# untitled_4.net
KiCad netlist of a schematic drawn in EAGLE
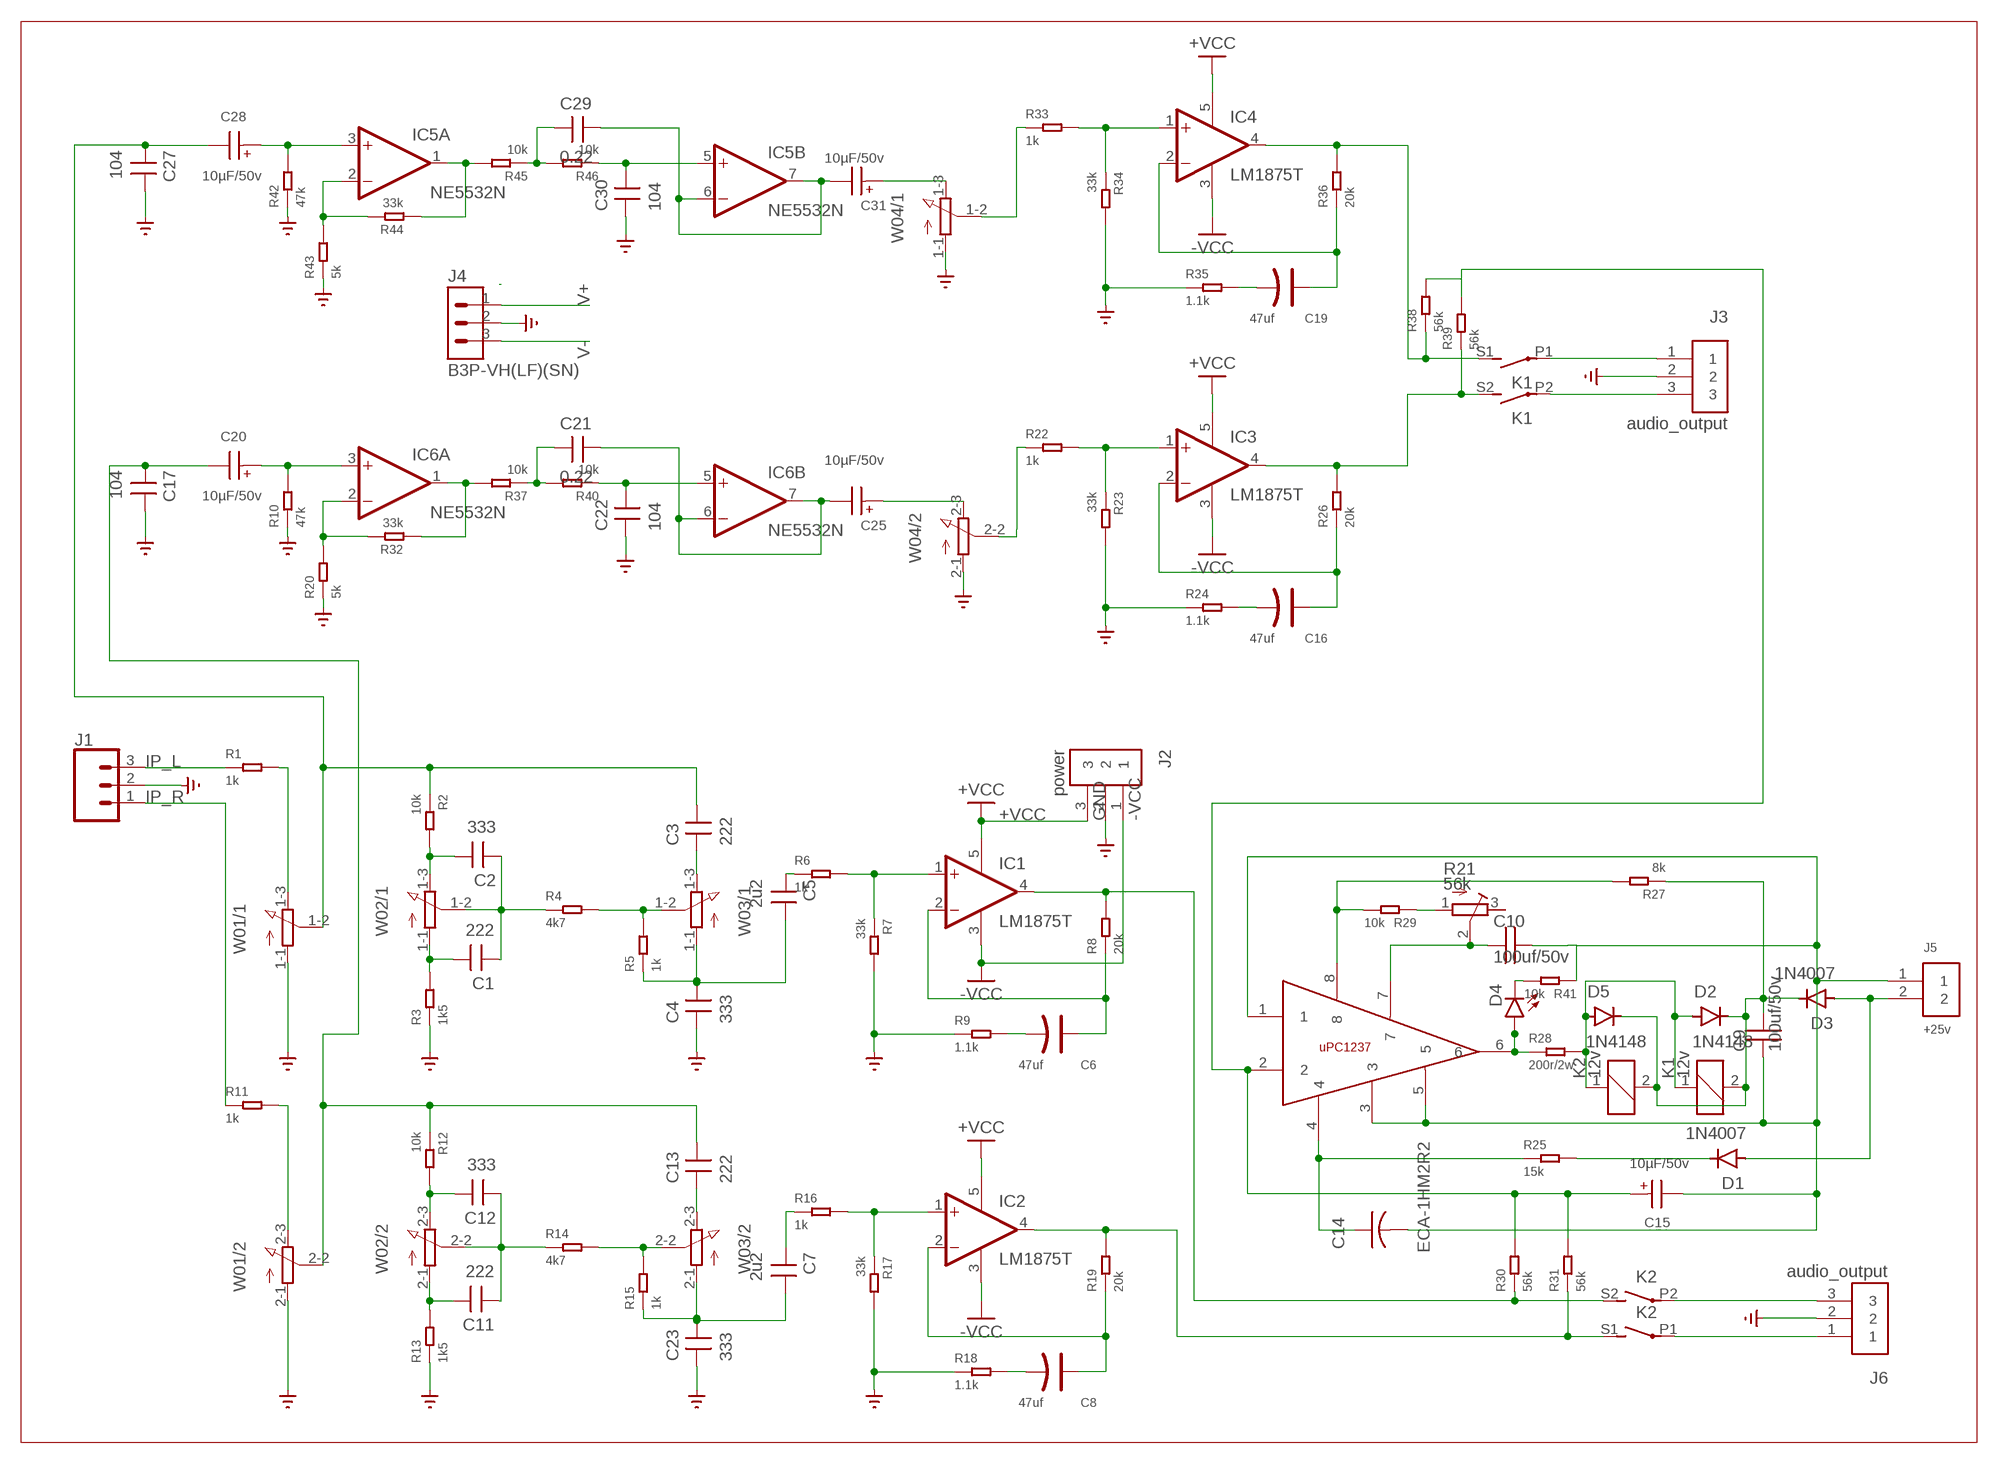
[diagram p0: schematic, sheet 1]

(export (version "E")
  (design (tool "Eeschema 10.0.6"))
  (components
    (comp (ref "C1")
      (value "222")
      (footprint "eagle-import:5.08MM-独石电容")
      (libsource (lib "eagle-import") (part "5.08MM-"))
    )
    (comp (ref "C2")
      (value "333")
      (footprint "eagle-import:5.08MM-独石电容")
      (libsource (lib "eagle-import") (part "5.08MM-"))
    )
    (comp (ref "C3")
      (value "222")
      (footprint "eagle-import:5.08MM-独石电容")
      (libsource (lib "eagle-import") (part "5.08MM-"))
    )
    (comp (ref "C4")
      (value "333")
      (footprint "eagle-import:5.08MM-独石电容")
      (libsource (lib "eagle-import") (part "5.08MM-"))
    )
    (comp (ref "C5")
      (value "2u2")
      (footprint "eagle-import:5.08MM-独石电容")
      (libsource (lib "eagle-import") (part "5.08MM-"))
    )
    (comp (ref "C6")
      (value "47uf")
      (footprint "eagle-import:PC-D5.3MM")
      (fields (field (name "MPN") "KS 100uF/16V"))
      (libsource (lib "eagle-import") (part "DIP-ALUMINUM-47UF-16V(D5-H7MM)"))
    )
    (comp (ref "C7")
      (value "2u2")
      (footprint "eagle-import:5.08MM-独石电容")
      (libsource (lib "eagle-import") (part "5.08MM-"))
    )
    (comp (ref "C8")
      (value "47uf")
      (footprint "eagle-import:PC-D5.3MM")
      (fields (field (name "MPN") "KS 100uF/16V"))
      (libsource (lib "eagle-import") (part "DIP-ALUMINUM-47UF-16V(D5-H7MM)"))
    )
    (comp (ref "C9")
      (value "100uf/50v")
      (footprint "eagle-import:8X12")
      (libsource (lib "eagle-import") (part "50V100UF8X12"))
    )
    (comp (ref "C10")
      (value "100uf/50v")
      (footprint "eagle-import:8X12")
      (libsource (lib "eagle-import") (part "50V100UF8X12"))
    )
    (comp (ref "C11")
      (value "222")
      (footprint "eagle-import:5.08MM-独石电容")
      (libsource (lib "eagle-import") (part "5.08MM-"))
    )
    (comp (ref "C12")
      (value "333")
      (footprint "eagle-import:5.08MM-独石电容")
      (libsource (lib "eagle-import") (part "5.08MM-"))
    )
    (comp (ref "C13")
      (value "222")
      (footprint "eagle-import:5.08MM-独石电容")
      (libsource (lib "eagle-import") (part "5.08MM-"))
    )
    (comp (ref "C14")
      (value "ECA-1HM2R2")
      (footprint "eagle-import:CAP_RADIAL_2MM")
      (fields
        (field (name "DIGIKEY_PART_NUMBER") "P5175-ND")
        (field (name "MANUFACTURER") "Panasonic Electronic Components")
        (field (name "CREATED_BY") "PCBLayout.com")
      )
      (libsource (lib "eagle-import") (part "ECA-1HM2R2"))
    )
    (comp (ref "C15")
      (value "10µF/50v")
      (footprint "eagle-import:WCAP-AT1H_5X11(DXL)")
      (libsource (lib "eagle-import") (part "WCAP-AT1H_5X11_860240272001"))
    )
    (comp (ref "C16")
      (value "47uf")
      (footprint "eagle-import:PC-D5.3MM")
      (fields (field (name "MPN") "KS 100uF/16V"))
      (libsource (lib "eagle-import") (part "DIP-ALUMINUM-47UF-16V(D5-H7MM)"))
    )
    (comp (ref "C17")
      (value "104")
      (footprint "eagle-import:5.08MM-独石电容")
      (libsource (lib "eagle-import") (part "5.08MM-"))
    )
    (comp (ref "C19")
      (value "47uf")
      (footprint "eagle-import:PC-D5.3MM")
      (fields (field (name "MPN") "KS 100uF/16V"))
      (libsource (lib "eagle-import") (part "DIP-ALUMINUM-47UF-16V(D5-H7MM)"))
    )
    (comp (ref "C20")
      (value "10µF/50v")
      (footprint "eagle-import:WCAP-AT1H_5X11(DXL)")
      (libsource (lib "eagle-import") (part "WCAP-AT1H_5X11_860240272001"))
    )
    (comp (ref "C21")
      (value "0.22")
      (footprint "eagle-import:5.08MM-独石电容")
      (libsource (lib "eagle-import") (part "5.08MM-"))
    )
    (comp (ref "C22")
      (value "104")
      (footprint "eagle-import:5.08MM-独石电容")
      (libsource (lib "eagle-import") (part "5.08MM-"))
    )
    (comp (ref "C23")
      (value "333")
      (footprint "eagle-import:5.08MM-独石电容")
      (libsource (lib "eagle-import") (part "5.08MM-"))
    )
    (comp (ref "C25")
      (value "10µF/50v")
      (footprint "eagle-import:WCAP-AT1H_5X11(DXL)")
      (libsource (lib "eagle-import") (part "WCAP-AT1H_5X11_860240272001"))
    )
    (comp (ref "C27")
      (value "104")
      (footprint "eagle-import:5.08MM-独石电容")
      (libsource (lib "eagle-import") (part "5.08MM-"))
    )
    (comp (ref "C28")
      (value "10µF/50v")
      (footprint "eagle-import:WCAP-AT1H_5X11(DXL)")
      (libsource (lib "eagle-import") (part "WCAP-AT1H_5X11_860240272001"))
    )
    (comp (ref "C29")
      (value "0.22")
      (footprint "eagle-import:5.08MM-独石电容")
      (libsource (lib "eagle-import") (part "5.08MM-"))
    )
    (comp (ref "C30")
      (value "104")
      (footprint "eagle-import:5.08MM-独石电容")
      (libsource (lib "eagle-import") (part "5.08MM-"))
    )
    (comp (ref "C31")
      (value "10µF/50v")
      (footprint "eagle-import:WCAP-AT1H_5X11(DXL)")
      (libsource (lib "eagle-import") (part "WCAP-AT1H_5X11_860240272001"))
    )
    (comp (ref "D1")
      (value "1N4007")
      (footprint "eagle-import:DO-41")
      (fields
        (field (name "DIGIKEY_PART_NUMBER") "1N4007MSCT-ND")
        (field (name "MANUFACTURER") "Micro Commercial Co")
        (field (name "CREATED_BY") "PCBLayout.com")
      )
      (libsource (lib "eagle-import") (part "1N4007"))
    )
    (comp (ref "D2")
      (value "1N4148")
      (footprint "eagle-import:DO-41")
      (fields
        (field (name "DIGIKEY_PART_NUMBER") "1N4007MSCT-ND")
        (field (name "MANUFACTURER") "Micro Commercial Co")
        (field (name "MPN") "1N4007")
        (field (name "CREATED_BY") "PCBLayout.com")
      )
      (libsource (lib "eagle-import") (part "1N4007"))
    )
    (comp (ref "D3")
      (value "1N4007")
      (footprint "eagle-import:DO-41")
      (fields
        (field (name "DIGIKEY_PART_NUMBER") "1N4007MSCT-ND")
        (field (name "MANUFACTURER") "Micro Commercial Co")
        (field (name "CREATED_BY") "PCBLayout.com")
      )
      (libsource (lib "eagle-import") (part "1N4007"))
    )
    (comp (ref "D4")
      (value "BEAGLEBONE_BLUE_LED-3MM-NO_SILK")
      (footprint "eagle-import:BEAGLEBONE_BLUE_BEAGLEBONE_BLUE_LED3MM-NS")
      (libsource (lib "eagle-import") (part "BEAGLEBONE_BLUE_LED-3MM-NO_SILK"))
    )
    (comp (ref "D5")
      (value "1N4148")
      (footprint "eagle-import:DO-41")
      (fields
        (field (name "DIGIKEY_PART_NUMBER") "1N4007MSCT-ND")
        (field (name "MANUFACTURER") "Micro Commercial Co")
        (field (name "MPN") "1N4007")
        (field (name "CREATED_BY") "PCBLayout.com")
      )
      (libsource (lib "eagle-import") (part "1N4007"))
    )
    (comp (ref "IC1")
      (value "LM1875T")
      (footprint "eagle-import:CB367")
      (libsource (lib "eagle-import") (part "LM1875T"))
    )
    (comp (ref "IC2")
      (value "LM1875T")
      (footprint "eagle-import:CB367")
      (libsource (lib "eagle-import") (part "LM1875T"))
    )
    (comp (ref "IC3")
      (value "LM1875T")
      (footprint "eagle-import:CB367")
      (libsource (lib "eagle-import") (part "LM1875T"))
    )
    (comp (ref "IC4")
      (value "LM1875T")
      (footprint "eagle-import:CB367")
      (libsource (lib "eagle-import") (part "LM1875T"))
    )
    (comp (ref "IC5")
      (value "NE5532N")
      (footprint "eagle-import:DIL08")
      (libsource (lib "eagle-import") (part "NE5532N"))
    )
    (comp (ref "IC6")
      (value "NE5532N")
      (footprint "eagle-import:DIL08")
      (libsource (lib "eagle-import") (part "NE5532N"))
    )
    (comp (ref "J1")
      (value "CONN_03POLAR")
      (footprint "eagle-import:MOLEX-1X3")
      (libsource (lib "eagle-import") (part "CONN_03POLAR"))
    )
    (comp (ref "J2")
      (value "power")
      (footprint "eagle-import:TERMINALBLOCK_PLUGGABLE-3-7.62MM")
      (fields
        (field (name "DIGIKEY_PART_NO") "732-2824-ND")
        (field (name "MANUFACTURER") "WURTH ELEKTRONIK")
        (field (name "MPN") "691311400103")
        (field (name "CREATED_BY") "PCBLayout.com")
      )
      (libsource (lib "eagle-import") (part "691311400103"))
    )
    (comp (ref "J3")
      (value "audio_output")
      (footprint "eagle-import:TERMINALBLOCK_PLUGGABLE-3-7.62MM")
      (fields
        (field (name "DIGIKEY_PART_NO") "732-2824-ND")
        (field (name "MANUFACTURER") "WURTH ELEKTRONIK")
        (field (name "MPN") "691311400103")
        (field (name "CREATED_BY") "PCBLayout.com")
      )
      (libsource (lib "eagle-import") (part "691311400103"))
    )
    (comp (ref "J4")
      (value "B3P-VH(LF)(SN)")
      (footprint "eagle-import:HDR-03")
      (fields
        (field (name "DIGIKEY_PART_NUMBER") "455-1640-ND")
        (field (name "MANUFACTURER") "JST Sales America Inc.")
        (field (name "CREATED_BY") "PCBLayout.com")
      )
      (libsource (lib "eagle-import") (part "B3P-VH(LF)(SN)"))
    )
    (comp (ref "J5")
      (value "+25v")
      (footprint "eagle-import:S2B-PH-K-S(LF)(SN)")
      (fields
        (field (name "DIGI_KEY_PART_NUMBER") "455-1719-ND")
        (field (name "MANUFACTURER") "JST Sales America Inc.")
        (field (name "MPN") "S2B-PH-K-S(LF)(SN)")
        (field (name "CREATED_BY") "PCBLayout.com")
      )
      (libsource (lib "eagle-import") (part "S2B-PH-K-S(LF)(SN)"))
    )
    (comp (ref "J6")
      (value "audio_output")
      (footprint "eagle-import:TERMINALBLOCK_PLUGGABLE-3-7.62MM")
      (fields
        (field (name "DIGIKEY_PART_NO") "732-2824-ND")
        (field (name "MANUFACTURER") "WURTH ELEKTRONIK")
        (field (name "MPN") "691311400103")
        (field (name "CREATED_BY") "PCBLayout.com")
      )
      (libsource (lib "eagle-import") (part "691311400103"))
    )
    (comp (ref "K1")
      (value "12v")
      (footprint "eagle-import:G2R2A")
      (fields (field (name "MPN") "G2R-2A-DC24"))
      (libsource (lib "eagle-import") (part "G2R2A"))
    )
    (comp (ref "K2")
      (value "12v")
      (footprint "eagle-import:G2R2A")
      (fields (field (name "MPN") "G2R-2A-DC24"))
      (libsource (lib "eagle-import") (part "G2R2A"))
    )
    (comp (ref "R1")
      (value "1k")
      (footprint "eagle-import:PR-D2.3XL6.5MM")
      (fields (field (name "MPN") "FHCFR-1/4W-105J"))
      (libsource (lib "eagle-import") (part "DIP-RES-1M-5%-1/4W(PR-D2.3XL6.5MM)"))
    )
    (comp (ref "R2")
      (value "10k")
      (footprint "eagle-import:PR-D2.3XL6.5MM")
      (fields (field (name "MPN") "FHCFR-1/4W-105J"))
      (libsource (lib "eagle-import") (part "DIP-RES-1M-5%-1/4W(PR-D2.3XL6.5MM)"))
    )
    (comp (ref "R3")
      (value "1k5")
      (footprint "eagle-import:PR-D2.3XL6.5MM")
      (fields (field (name "MPN") "FHCFR-1/4W-105J"))
      (libsource (lib "eagle-import") (part "DIP-RES-1M-5%-1/4W(PR-D2.3XL6.5MM)"))
    )
    (comp (ref "R4")
      (value "4k7")
      (footprint "eagle-import:PR-D2.3XL6.5MM")
      (fields (field (name "MPN") "FHCFR-1/4W-105J"))
      (libsource (lib "eagle-import") (part "DIP-RES-1M-5%-1/4W(PR-D2.3XL6.5MM)"))
    )
    (comp (ref "R5")
      (value "1k")
      (footprint "eagle-import:PR-D2.3XL6.5MM")
      (fields (field (name "MPN") "FHCFR-1/4W-105J"))
      (libsource (lib "eagle-import") (part "DIP-RES-1M-5%-1/4W(PR-D2.3XL6.5MM)"))
    )
    (comp (ref "R6")
      (value "1k")
      (footprint "eagle-import:PR-D2.3XL6.5MM")
      (fields (field (name "MPN") "FHCFR-1/4W-105J"))
      (libsource (lib "eagle-import") (part "DIP-RES-1M-5%-1/4W(PR-D2.3XL6.5MM)"))
    )
    (comp (ref "R7")
      (value "33k")
      (footprint "eagle-import:PR-D2.3XL6.5MM")
      (fields (field (name "MPN") "FHCFR-1/4W-105J"))
      (libsource (lib "eagle-import") (part "DIP-RES-1M-5%-1/4W(PR-D2.3XL6.5MM)"))
    )
    (comp (ref "R8")
      (value "20k")
      (footprint "eagle-import:PR-D2.3XL6.5MM")
      (fields (field (name "MPN") "FHCFR-1/4W-105J"))
      (libsource (lib "eagle-import") (part "DIP-RES-1M-5%-1/4W(PR-D2.3XL6.5MM)"))
    )
    (comp (ref "R9")
      (value "1.1k")
      (footprint "eagle-import:PR-D2.3XL6.5MM")
      (fields (field (name "MPN") "FHCFR-1/4W-105J"))
      (libsource (lib "eagle-import") (part "DIP-RES-1M-5%-1/4W(PR-D2.3XL6.5MM)"))
    )
    (comp (ref "R10")
      (value "47k")
      (footprint "eagle-import:PR-D2.3XL6.5MM")
      (fields (field (name "MPN") "FHCFR-1/4W-105J"))
      (libsource (lib "eagle-import") (part "DIP-RES-1M-5%-1/4W(PR-D2.3XL6.5MM)"))
    )
    (comp (ref "R11")
      (value "1k")
      (footprint "eagle-import:PR-D2.3XL6.5MM")
      (fields (field (name "MPN") "FHCFR-1/4W-105J"))
      (libsource (lib "eagle-import") (part "DIP-RES-1M-5%-1/4W(PR-D2.3XL6.5MM)"))
    )
    (comp (ref "R12")
      (value "10k")
      (footprint "eagle-import:PR-D2.3XL6.5MM")
      (fields (field (name "MPN") "FHCFR-1/4W-105J"))
      (libsource (lib "eagle-import") (part "DIP-RES-1M-5%-1/4W(PR-D2.3XL6.5MM)"))
    )
    (comp (ref "R13")
      (value "1k5")
      (footprint "eagle-import:PR-D2.3XL6.5MM")
      (fields (field (name "MPN") "FHCFR-1/4W-105J"))
      (libsource (lib "eagle-import") (part "DIP-RES-1M-5%-1/4W(PR-D2.3XL6.5MM)"))
    )
    (comp (ref "R14")
      (value "4k7")
      (footprint "eagle-import:PR-D2.3XL6.5MM")
      (fields (field (name "MPN") "FHCFR-1/4W-105J"))
      (libsource (lib "eagle-import") (part "DIP-RES-1M-5%-1/4W(PR-D2.3XL6.5MM)"))
    )
    (comp (ref "R15")
      (value "1k")
      (footprint "eagle-import:PR-D2.3XL6.5MM")
      (fields (field (name "MPN") "FHCFR-1/4W-105J"))
      (libsource (lib "eagle-import") (part "DIP-RES-1M-5%-1/4W(PR-D2.3XL6.5MM)"))
    )
    (comp (ref "R16")
      (value "1k")
      (footprint "eagle-import:PR-D2.3XL6.5MM")
      (fields (field (name "MPN") "FHCFR-1/4W-105J"))
      (libsource (lib "eagle-import") (part "DIP-RES-1M-5%-1/4W(PR-D2.3XL6.5MM)"))
    )
    (comp (ref "R17")
      (value "33k")
      (footprint "eagle-import:PR-D2.3XL6.5MM")
      (fields (field (name "MPN") "FHCFR-1/4W-105J"))
      (libsource (lib "eagle-import") (part "DIP-RES-1M-5%-1/4W(PR-D2.3XL6.5MM)"))
    )
    (comp (ref "R18")
      (value "1.1k")
      (footprint "eagle-import:PR-D2.3XL6.5MM")
      (fields (field (name "MPN") "FHCFR-1/4W-105J"))
      (libsource (lib "eagle-import") (part "DIP-RES-1M-5%-1/4W(PR-D2.3XL6.5MM)"))
    )
    (comp (ref "R19")
      (value "20k")
      (footprint "eagle-import:PR-D2.3XL6.5MM")
      (fields (field (name "MPN") "FHCFR-1/4W-105J"))
      (libsource (lib "eagle-import") (part "DIP-RES-1M-5%-1/4W(PR-D2.3XL6.5MM)"))
    )
    (comp (ref "R20")
      (value "5k")
      (footprint "eagle-import:PR-D2.3XL6.5MM")
      (fields (field (name "MPN") "FHCFR-1/4W-105J"))
      (libsource (lib "eagle-import") (part "DIP-RES-1M-5%-1/4W(PR-D2.3XL6.5MM)"))
    )
    (comp (ref "R21")
      (value "56k")
      (footprint "eagle-import:RTRIM3296W")
      (libsource (lib "eagle-import") (part "R-TRIMM3296W"))
    )
    (comp (ref "R22")
      (value "1k")
      (footprint "eagle-import:PR-D2.3XL6.5MM")
      (fields (field (name "MPN") "FHCFR-1/4W-105J"))
      (libsource (lib "eagle-import") (part "DIP-RES-1M-5%-1/4W(PR-D2.3XL6.5MM)"))
    )
    (comp (ref "R23")
      (value "33k")
      (footprint "eagle-import:PR-D2.3XL6.5MM")
      (fields (field (name "MPN") "FHCFR-1/4W-105J"))
      (libsource (lib "eagle-import") (part "DIP-RES-1M-5%-1/4W(PR-D2.3XL6.5MM)"))
    )
    (comp (ref "R24")
      (value "1.1k")
      (footprint "eagle-import:PR-D2.3XL6.5MM")
      (fields (field (name "MPN") "FHCFR-1/4W-105J"))
      (libsource (lib "eagle-import") (part "DIP-RES-1M-5%-1/4W(PR-D2.3XL6.5MM)"))
    )
    (comp (ref "R25")
      (value "15k")
      (footprint "eagle-import:PR-D2.3XL6.5MM")
      (fields (field (name "MPN") "FHCFR-1/4W-105J"))
      (libsource (lib "eagle-import") (part "DIP-RES-1M-5%-1/4W(PR-D2.3XL6.5MM)"))
    )
    (comp (ref "R26")
      (value "20k")
      (footprint "eagle-import:PR-D2.3XL6.5MM")
      (fields (field (name "MPN") "FHCFR-1/4W-105J"))
      (libsource (lib "eagle-import") (part "DIP-RES-1M-5%-1/4W(PR-D2.3XL6.5MM)"))
    )
    (comp (ref "R27")
      (value "8k")
      (footprint "eagle-import:PR-D2.3XL6.5MM")
      (fields (field (name "MPN") "FHCFR-1/4W-105J"))
      (libsource (lib "eagle-import") (part "DIP-RES-1M-5%-1/4W(PR-D2.3XL6.5MM)"))
    )
    (comp (ref "R28")
      (value "200r/2w")
      (footprint "eagle-import:PR-D2.3XL6.5MM")
      (fields (field (name "MPN") "FHCFR-1/4W-105J"))
      (libsource (lib "eagle-import") (part "DIP-RES-1M-5%-1/4W(PR-D2.3XL6.5MM)"))
    )
    (comp (ref "R29")
      (value "10k")
      (footprint "eagle-import:PR-D2.3XL6.5MM")
      (fields (field (name "MPN") "FHCFR-1/4W-105J"))
      (libsource (lib "eagle-import") (part "DIP-RES-1M-5%-1/4W(PR-D2.3XL6.5MM)"))
    )
    (comp (ref "R30")
      (value "56k")
      (footprint "eagle-import:PR-D2.3XL6.5MM")
      (fields (field (name "MPN") "FHCFR-1/4W-105J"))
      (libsource (lib "eagle-import") (part "DIP-RES-1M-5%-1/4W(PR-D2.3XL6.5MM)"))
    )
    (comp (ref "R31")
      (value "56k")
      (footprint "eagle-import:PR-D2.3XL6.5MM")
      (fields (field (name "MPN") "FHCFR-1/4W-105J"))
      (libsource (lib "eagle-import") (part "DIP-RES-1M-5%-1/4W(PR-D2.3XL6.5MM)"))
    )
    (comp (ref "R32")
      (value "33k")
      (footprint "eagle-import:PR-D2.3XL6.5MM")
      (fields (field (name "MPN") "FHCFR-1/4W-105J"))
      (libsource (lib "eagle-import") (part "DIP-RES-1M-5%-1/4W(PR-D2.3XL6.5MM)"))
    )
    (comp (ref "R33")
      (value "1k")
      (footprint "eagle-import:PR-D2.3XL6.5MM")
      (fields (field (name "MPN") "FHCFR-1/4W-105J"))
      (libsource (lib "eagle-import") (part "DIP-RES-1M-5%-1/4W(PR-D2.3XL6.5MM)"))
    )
    (comp (ref "R34")
      (value "33k")
      (footprint "eagle-import:PR-D2.3XL6.5MM")
      (fields (field (name "MPN") "FHCFR-1/4W-105J"))
      (libsource (lib "eagle-import") (part "DIP-RES-1M-5%-1/4W(PR-D2.3XL6.5MM)"))
    )
    (comp (ref "R35")
      (value "1.1k")
      (footprint "eagle-import:PR-D2.3XL6.5MM")
      (fields (field (name "MPN") "FHCFR-1/4W-105J"))
      (libsource (lib "eagle-import") (part "DIP-RES-1M-5%-1/4W(PR-D2.3XL6.5MM)"))
    )
    (comp (ref "R36")
      (value "20k")
      (footprint "eagle-import:PR-D2.3XL6.5MM")
      (fields (field (name "MPN") "FHCFR-1/4W-105J"))
      (libsource (lib "eagle-import") (part "DIP-RES-1M-5%-1/4W(PR-D2.3XL6.5MM)"))
    )
    (comp (ref "R37")
      (value "10k")
      (footprint "eagle-import:PR-D2.3XL6.5MM")
      (fields (field (name "MPN") "FHCFR-1/4W-105J"))
      (libsource (lib "eagle-import") (part "DIP-RES-1M-5%-1/4W(PR-D2.3XL6.5MM)"))
    )
    (comp (ref "R38")
      (value "56k")
      (footprint "eagle-import:PR-D2.3XL6.5MM")
      (fields (field (name "MPN") "FHCFR-1/4W-105J"))
      (libsource (lib "eagle-import") (part "DIP-RES-1M-5%-1/4W(PR-D2.3XL6.5MM)"))
    )
    (comp (ref "R39")
      (value "56k")
      (footprint "eagle-import:PR-D2.3XL6.5MM")
      (fields (field (name "MPN") "FHCFR-1/4W-105J"))
      (libsource (lib "eagle-import") (part "DIP-RES-1M-5%-1/4W(PR-D2.3XL6.5MM)"))
    )
    (comp (ref "R40")
      (value "10k")
      (footprint "eagle-import:PR-D2.3XL6.5MM")
      (fields (field (name "MPN") "FHCFR-1/4W-105J"))
      (libsource (lib "eagle-import") (part "DIP-RES-1M-5%-1/4W(PR-D2.3XL6.5MM)"))
    )
    (comp (ref "R41")
      (value "10k")
      (footprint "eagle-import:PR-D2.3XL6.5MM")
      (fields (field (name "MPN") "FHCFR-1/4W-105J"))
      (libsource (lib "eagle-import") (part "DIP-RES-1M-5%-1/4W(PR-D2.3XL6.5MM)"))
    )
    (comp (ref "R42")
      (value "47k")
      (footprint "eagle-import:PR-D2.3XL6.5MM")
      (fields (field (name "MPN") "FHCFR-1/4W-105J"))
      (libsource (lib "eagle-import") (part "DIP-RES-1M-5%-1/4W(PR-D2.3XL6.5MM)"))
    )
    (comp (ref "R43")
      (value "5k")
      (footprint "eagle-import:PR-D2.3XL6.5MM")
      (fields (field (name "MPN") "FHCFR-1/4W-105J"))
      (libsource (lib "eagle-import") (part "DIP-RES-1M-5%-1/4W(PR-D2.3XL6.5MM)"))
    )
    (comp (ref "R44")
      (value "33k")
      (footprint "eagle-import:PR-D2.3XL6.5MM")
      (fields (field (name "MPN") "FHCFR-1/4W-105J"))
      (libsource (lib "eagle-import") (part "DIP-RES-1M-5%-1/4W(PR-D2.3XL6.5MM)"))
    )
    (comp (ref "R45")
      (value "10k")
      (footprint "eagle-import:PR-D2.3XL6.5MM")
      (fields (field (name "MPN") "FHCFR-1/4W-105J"))
      (libsource (lib "eagle-import") (part "DIP-RES-1M-5%-1/4W(PR-D2.3XL6.5MM)"))
    )
    (comp (ref "R46")
      (value "10k")
      (footprint "eagle-import:PR-D2.3XL6.5MM")
      (fields (field (name "MPN") "FHCFR-1/4W-105J"))
      (libsource (lib "eagle-import") (part "DIP-RES-1M-5%-1/4W(PR-D2.3XL6.5MM)"))
    )
    (comp (ref "U2")
      (value "UPC1237HA")
      (footprint "eagle-import:SIP8")
      (libsource (lib "eagle-import") (part "UPC1237HA"))
    )
    (comp (ref "W01")
      (value "3RP/1610G")
      (footprint "eagle-import:3RP_1610G")
      (libsource (lib "eagle-import") (part "3RP/1610G"))
    )
    (comp (ref "W02")
      (value "3RP/1610G")
      (footprint "eagle-import:3RP_1610G")
      (libsource (lib "eagle-import") (part "3RP/1610G"))
    )
    (comp (ref "W03")
      (value "3RP/1610G")
      (footprint "eagle-import:3RP_1610G")
      (libsource (lib "eagle-import") (part "3RP/1610G"))
    )
    (comp (ref "W04")
      (value "3RP/1610G")
      (footprint "eagle-import:3RP_1610G")
      (libsource (lib "eagle-import") (part "3RP/1610G"))
    )
  )
  (nets
    (net (code "1") (name "+VCC") (class "Default")
      (node (ref "IC1") (pin "5") (pinfunction "V+_5") (pintype "power_in"))
      (node (ref "IC2") (pin "5") (pinfunction "V+_5") (pintype "power_in"))
      (node (ref "IC3") (pin "5") (pinfunction "V+_5") (pintype "power_in"))
      (node (ref "IC4") (pin "5") (pinfunction "V+_5") (pintype "power_in"))
      (node (ref "J2") (pin "3") (pinfunction "3_3") (pintype "passive"))
    )
    (net (code "2") (name "-VCC") (class "Default")
      (node (ref "IC1") (pin "3") (pinfunction "V-_3") (pintype "power_in"))
      (node (ref "IC2") (pin "3") (pinfunction "V-_3") (pintype "power_in"))
      (node (ref "IC3") (pin "3") (pinfunction "V-_3") (pintype "power_in"))
      (node (ref "IC4") (pin "3") (pinfunction "V-_3") (pintype "power_in"))
      (node (ref "J2") (pin "1") (pinfunction "1_1") (pintype "passive"))
    )
    (net (code "3") (name "/IP_L") (class "Default")
      (node (ref "J1") (pin "3") (pinfunction "3_3") (pintype "passive"))
      (node (ref "R1") (pin "1") (pinfunction "1_1") (pintype "passive"))
    )
    (net (code "4") (name "/IP_R") (class "Default")
      (node (ref "J1") (pin "1") (pinfunction "1_1") (pintype "passive"))
      (node (ref "R11") (pin "1") (pinfunction "1_1") (pintype "passive"))
    )
    (net (code "5") (name "/V+") (class "Default")
      (node (ref "J4") (pin "1") (pinfunction "1_1") (pintype "passive"))
    )
    (net (code "6") (name "/V-") (class "Default")
      (node (ref "J4") (pin "3") (pinfunction "3_3") (pintype "passive"))
    )
    (net (code "7") (name "Net-(C1-1)") (class "Default")
      (node (ref "C1") (pin "P$2") (pinfunction "1_P$2") (pintype "bidirectional"))
      (node (ref "C2") (pin "P$2") (pinfunction "1_P$2") (pintype "bidirectional"))
      (node (ref "R4") (pin "1") (pinfunction "1_1") (pintype "passive"))
      (node (ref "W02") (pin "1-2") (pinfunction "S_1-2") (pintype "passive"))
    )
    (net (code "8") (name "Net-(C1-2)") (class "Default")
      (node (ref "C1") (pin "P$1") (pinfunction "2_P$1") (pintype "bidirectional"))
      (node (ref "R3") (pin "2") (pinfunction "2_2") (pintype "passive"))
      (node (ref "W02") (pin "1-1") (pinfunction "A_1-1") (pintype "passive"))
    )
    (net (code "9") (name "Net-(C2-2)") (class "Default")
      (node (ref "C2") (pin "P$1") (pinfunction "2_P$1") (pintype "bidirectional"))
      (node (ref "R2") (pin "2") (pinfunction "2_2") (pintype "passive"))
      (node (ref "W02") (pin "1-3") (pinfunction "E_1-3") (pintype "passive"))
    )
    (net (code "10") (name "Net-(C3-1)") (class "Default")
      (node (ref "C3") (pin "P$2") (pinfunction "1_P$2") (pintype "bidirectional"))
      (node (ref "W03") (pin "1-3") (pinfunction "E_1-3") (pintype "passive"))
    )
    (net (code "11") (name "Net-(C4-2)") (class "Default")
      (node (ref "C4") (pin "P$1") (pinfunction "2_P$1") (pintype "bidirectional"))
      (node (ref "C5") (pin "P$1") (pinfunction "2_P$1") (pintype "bidirectional"))
      (node (ref "R5") (pin "1") (pinfunction "1_1") (pintype "passive"))
      (node (ref "W03") (pin "1-1") (pinfunction "A_1-1") (pintype "passive"))
    )
    (net (code "12") (name "Net-(C5-1)") (class "Default")
      (node (ref "C5") (pin "P$2") (pinfunction "1_P$2") (pintype "bidirectional"))
      (node (ref "R6") (pin "1") (pinfunction "1_1") (pintype "passive"))
    )
    (net (code "13") (name "Net-(C6-Pad-)") (class "Default")
      (node (ref "C6") (pin "-") (pinfunction "-_-") (pintype "passive"))
      (node (ref "R9") (pin "2") (pinfunction "2_2") (pintype "passive"))
    )
    (net (code "14") (name "Net-(C7-1)") (class "Default")
      (node (ref "C7") (pin "P$2") (pinfunction "1_P$2") (pintype "bidirectional"))
      (node (ref "R16") (pin "1") (pinfunction "1_1") (pintype "passive"))
    )
    (net (code "15") (name "Net-(C8-Pad-)") (class "Default")
      (node (ref "C8") (pin "-") (pinfunction "-_-") (pintype "passive"))
      (node (ref "R18") (pin "2") (pinfunction "2_2") (pintype "passive"))
    )
    (net (code "16") (name "Net-(C9-Pad2)") (class "Default")
      (node (ref "C9") (pin "2") (pinfunction "2_2") (pintype "bidirectional"))
      (node (ref "D2") (pin "C") (pinfunction "C_C") (pintype "passive"))
      (node (ref "D3") (pin "C") (pinfunction "C_C") (pintype "passive"))
      (node (ref "D5") (pin "C") (pinfunction "C_C") (pintype "passive"))
      (node (ref "K1") (pin "2") (pinfunction "2_2") (pintype "passive"))
      (node (ref "K2") (pin "2") (pinfunction "2_2") (pintype "passive"))
      (node (ref "R27") (pin "1") (pinfunction "1_1") (pintype "passive"))
    )
    (net (code "17") (name "Net-(C11-1)") (class "Default")
      (node (ref "C11") (pin "P$2") (pinfunction "1_P$2") (pintype "bidirectional"))
      (node (ref "C12") (pin "P$2") (pinfunction "1_P$2") (pintype "bidirectional"))
      (node (ref "R14") (pin "1") (pinfunction "1_1") (pintype "passive"))
      (node (ref "W02") (pin "2-2") (pinfunction "S_2-2") (pintype "passive"))
    )
    (net (code "18") (name "Net-(C11-2)") (class "Default")
      (node (ref "C11") (pin "P$1") (pinfunction "2_P$1") (pintype "bidirectional"))
      (node (ref "R13") (pin "2") (pinfunction "2_2") (pintype "passive"))
      (node (ref "W02") (pin "2-1") (pinfunction "A_2-1") (pintype "passive"))
    )
    (net (code "19") (name "Net-(C12-2)") (class "Default")
      (node (ref "C12") (pin "P$1") (pinfunction "2_P$1") (pintype "bidirectional"))
      (node (ref "R12") (pin "2") (pinfunction "2_2") (pintype "passive"))
      (node (ref "W02") (pin "2-3") (pinfunction "E_2-3") (pintype "passive"))
    )
    (net (code "20") (name "Net-(C13-1)") (class "Default")
      (node (ref "C13") (pin "P$2") (pinfunction "1_P$2") (pintype "bidirectional"))
      (node (ref "W03") (pin "2-3") (pinfunction "E_2-3") (pintype "passive"))
    )
    (net (code "21") (name "Net-(C13-2)") (class "Default")
      (node (ref "C13") (pin "P$1") (pinfunction "2_P$1") (pintype "bidirectional"))
      (node (ref "C17") (pin "P$2") (pinfunction "1_P$2") (pintype "bidirectional"))
      (node (ref "C20") (pin "2") (pinfunction "-_2") (pintype "passive"))
      (node (ref "R12") (pin "1") (pinfunction "1_1") (pintype "passive"))
      (node (ref "W01") (pin "2-2") (pinfunction "S_2-2") (pintype "passive"))
    )
    (net (code "22") (name "Net-(C14-Pad1)") (class "Default")
      (node (ref "C14") (pin "1") (pinfunction "1_1") (pintype "passive"))
      (node (ref "R25") (pin "1") (pinfunction "1_1") (pintype "passive"))
      (node (ref "U2") (pin "4") (pinfunction "4_4") (pintype "bidirectional"))
    )
    (net (code "23") (name "Net-(C15-+)") (class "Default")
      (node (ref "C15") (pin "1") (pinfunction "+_1") (pintype "passive"))
      (node (ref "R30") (pin "2") (pinfunction "2_2") (pintype "passive"))
      (node (ref "R31") (pin "2") (pinfunction "2_2") (pintype "passive"))
      (node (ref "R38") (pin "2") (pinfunction "2_2") (pintype "passive"))
      (node (ref "R39") (pin "2") (pinfunction "2_2") (pintype "passive"))
      (node (ref "U2") (pin "2") (pinfunction "2_2") (pintype "bidirectional"))
    )
    (net (code "24") (name "Net-(C15--)") (class "Default")
      (node (ref "C10") (pin "2") (pinfunction "2_2") (pintype "bidirectional"))
      (node (ref "C14") (pin "2") (pinfunction "2_2") (pintype "passive"))
      (node (ref "C15") (pin "2") (pinfunction "-_2") (pintype "passive"))
      (node (ref "C9") (pin "1") (pinfunction "1_1") (pintype "bidirectional"))
      (node (ref "J5") (pin "1") (pinfunction "1_1") (pintype "passive"))
      (node (ref "R41") (pin "1") (pinfunction "1_1") (pintype "passive"))
      (node (ref "U2") (pin "1") (pinfunction "1_1") (pintype "bidirectional"))
      (node (ref "U2") (pin "3") (pinfunction "3_3") (pintype "bidirectional"))
      (node (ref "U2") (pin "5") (pinfunction "5_5") (pintype "bidirectional"))
    )
    (net (code "25") (name "Net-(C16-Pad-)") (class "Default")
      (node (ref "C16") (pin "-") (pinfunction "-_-") (pintype "passive"))
      (node (ref "R24") (pin "2") (pinfunction "2_2") (pintype "passive"))
    )
    (net (code "26") (name "Net-(C19-Pad-)") (class "Default")
      (node (ref "C19") (pin "-") (pinfunction "-_-") (pintype "passive"))
      (node (ref "R35") (pin "2") (pinfunction "2_2") (pintype "passive"))
    )
    (net (code "27") (name "Net-(C20-+)") (class "Default")
      (node (ref "C20") (pin "1") (pinfunction "+_1") (pintype "passive"))
      (node (ref "IC6") (pin "3") (pinfunction "+IN_3") (pintype "input"))
      (node (ref "R10") (pin "2") (pinfunction "2_2") (pintype "passive"))
    )
    (net (code "28") (name "Net-(C21-1)") (class "Default")
      (node (ref "C21") (pin "P$2") (pinfunction "1_P$2") (pintype "bidirectional"))
      (node (ref "R37") (pin "1") (pinfunction "1_1") (pintype "passive"))
      (node (ref "R40") (pin "2") (pinfunction "2_2") (pintype "passive"))
    )
    (net (code "29") (name "Net-(C21-2)") (class "Default")
      (node (ref "C21") (pin "P$1") (pinfunction "2_P$1") (pintype "bidirectional"))
      (node (ref "C25") (pin "2") (pinfunction "-_2") (pintype "passive"))
      (node (ref "IC6") (pin "6") (pinfunction "-IN_6") (pintype "input"))
      (node (ref "IC6") (pin "7") (pinfunction "OUT_7") (pintype "output"))
    )
    (net (code "30") (name "Net-(C22-2)") (class "Default")
      (node (ref "C22") (pin "P$1") (pinfunction "2_P$1") (pintype "bidirectional"))
      (node (ref "IC6") (pin "5") (pinfunction "+IN_5") (pintype "input"))
      (node (ref "R40") (pin "1") (pinfunction "1_1") (pintype "passive"))
    )
    (net (code "31") (name "Net-(C23-2)") (class "Default")
      (node (ref "C23") (pin "P$1") (pinfunction "2_P$1") (pintype "bidirectional"))
      (node (ref "C7") (pin "P$1") (pinfunction "2_P$1") (pintype "bidirectional"))
      (node (ref "R15") (pin "1") (pinfunction "1_1") (pintype "passive"))
      (node (ref "W03") (pin "2-1") (pinfunction "A_2-1") (pintype "passive"))
    )
    (net (code "32") (name "Net-(C25-+)") (class "Default")
      (node (ref "C25") (pin "1") (pinfunction "+_1") (pintype "passive"))
      (node (ref "W04") (pin "2-3") (pinfunction "E_2-3") (pintype "passive"))
    )
    (net (code "33") (name "Net-(C27-1)") (class "Default")
      (node (ref "C27") (pin "P$2") (pinfunction "1_P$2") (pintype "bidirectional"))
      (node (ref "C28") (pin "2") (pinfunction "-_2") (pintype "passive"))
      (node (ref "C3") (pin "P$1") (pinfunction "2_P$1") (pintype "bidirectional"))
      (node (ref "R2") (pin "1") (pinfunction "1_1") (pintype "passive"))
      (node (ref "W01") (pin "1-2") (pinfunction "S_1-2") (pintype "passive"))
    )
    (net (code "34") (name "Net-(C28-+)") (class "Default")
      (node (ref "C28") (pin "1") (pinfunction "+_1") (pintype "passive"))
      (node (ref "IC5") (pin "3") (pinfunction "+IN_3") (pintype "input"))
      (node (ref "R42") (pin "2") (pinfunction "2_2") (pintype "passive"))
    )
    (net (code "35") (name "Net-(C29-1)") (class "Default")
      (node (ref "C29") (pin "P$2") (pinfunction "1_P$2") (pintype "bidirectional"))
      (node (ref "R45") (pin "1") (pinfunction "1_1") (pintype "passive"))
      (node (ref "R46") (pin "2") (pinfunction "2_2") (pintype "passive"))
    )
    (net (code "36") (name "Net-(C29-2)") (class "Default")
      (node (ref "C29") (pin "P$1") (pinfunction "2_P$1") (pintype "bidirectional"))
      (node (ref "C31") (pin "2") (pinfunction "-_2") (pintype "passive"))
      (node (ref "IC5") (pin "6") (pinfunction "-IN_6") (pintype "input"))
      (node (ref "IC5") (pin "7") (pinfunction "OUT_7") (pintype "output"))
    )
    (net (code "37") (name "Net-(C30-2)") (class "Default")
      (node (ref "C30") (pin "P$1") (pinfunction "2_P$1") (pintype "bidirectional"))
      (node (ref "IC5") (pin "5") (pinfunction "+IN_5") (pintype "input"))
      (node (ref "R46") (pin "1") (pinfunction "1_1") (pintype "passive"))
    )
    (net (code "38") (name "Net-(C31-+)") (class "Default")
      (node (ref "C31") (pin "1") (pinfunction "+_1") (pintype "passive"))
      (node (ref "W04") (pin "1-3") (pinfunction "E_1-3") (pintype "passive"))
    )
    (net (code "39") (name "Net-(D1-PadA)") (class "Default")
      (node (ref "D1") (pin "A") (pinfunction "A_A") (pintype "passive"))
      (node (ref "D3") (pin "A") (pinfunction "A_A") (pintype "passive"))
      (node (ref "J5") (pin "2") (pinfunction "2_2") (pintype "passive"))
    )
    (net (code "40") (name "Net-(D1-PadC)") (class "Default")
      (node (ref "D1") (pin "C") (pinfunction "C_C") (pintype "passive"))
      (node (ref "R25") (pin "2") (pinfunction "2_2") (pintype "passive"))
    )
    (net (code "41") (name "Net-(D2-PadA)") (class "Default")
      (node (ref "D2") (pin "A") (pinfunction "A_A") (pintype "passive"))
      (node (ref "D5") (pin "A") (pinfunction "A_A") (pintype "passive"))
      (node (ref "K1") (pin "1") (pinfunction "1_1") (pintype "passive"))
      (node (ref "K2") (pin "1") (pinfunction "1_1") (pintype "passive"))
      (node (ref "R28") (pin "2") (pinfunction "2_2") (pintype "passive"))
    )
    (net (code "42") (name "Net-(D4-C)") (class "Default")
      (node (ref "D4") (pin "K") (pinfunction "C_K") (pintype "passive"))
      (node (ref "R41") (pin "2") (pinfunction "2_2") (pintype "passive"))
    )
    (net (code "43") (name "Net-(D4-PadA)") (class "Default")
      (node (ref "D4") (pin "A") (pinfunction "A_A") (pintype "passive"))
      (node (ref "R28") (pin "1") (pinfunction "1_1") (pintype "passive"))
      (node (ref "U2") (pin "6") (pinfunction "6_6") (pintype "bidirectional"))
    )
    (net (code "44") (name "Net-(IC1-+IN)") (class "Default")
      (node (ref "IC1") (pin "1") (pinfunction "+IN_1") (pintype "input"))
      (node (ref "R6") (pin "2") (pinfunction "2_2") (pintype "passive"))
      (node (ref "R7") (pin "1") (pinfunction "1_1") (pintype "passive"))
    )
    (net (code "45") (name "Net-(IC1--IN)") (class "Default")
      (node (ref "C6") (pin "+") (pinfunction "+_+") (pintype "passive"))
      (node (ref "IC1") (pin "2") (pinfunction "-IN_2") (pintype "input"))
      (node (ref "R8") (pin "1") (pinfunction "1_1") (pintype "passive"))
    )
    (net (code "46") (name "Net-(IC1-OUT)") (class "Default")
      (node (ref "IC1") (pin "4") (pinfunction "OUT_4") (pintype "output"))
      (node (ref "K2") (pin "S2") (pinfunction "S_S2") (pintype "passive"))
      (node (ref "R30") (pin "1") (pinfunction "1_1") (pintype "passive"))
      (node (ref "R8") (pin "2") (pinfunction "2_2") (pintype "passive"))
    )
    (net (code "47") (name "Net-(IC2-+IN)") (class "Default")
      (node (ref "IC2") (pin "1") (pinfunction "+IN_1") (pintype "input"))
      (node (ref "R16") (pin "2") (pinfunction "2_2") (pintype "passive"))
      (node (ref "R17") (pin "1") (pinfunction "1_1") (pintype "passive"))
    )
    (net (code "48") (name "Net-(IC2--IN)") (class "Default")
      (node (ref "C8") (pin "+") (pinfunction "+_+") (pintype "passive"))
      (node (ref "IC2") (pin "2") (pinfunction "-IN_2") (pintype "input"))
      (node (ref "R19") (pin "1") (pinfunction "1_1") (pintype "passive"))
    )
    (net (code "49") (name "Net-(IC2-OUT)") (class "Default")
      (node (ref "IC2") (pin "4") (pinfunction "OUT_4") (pintype "output"))
      (node (ref "K2") (pin "S1") (pinfunction "S_S1") (pintype "passive"))
      (node (ref "R19") (pin "2") (pinfunction "2_2") (pintype "passive"))
      (node (ref "R31") (pin "1") (pinfunction "1_1") (pintype "passive"))
    )
    (net (code "50") (name "Net-(IC3-+IN)") (class "Default")
      (node (ref "IC3") (pin "1") (pinfunction "+IN_1") (pintype "input"))
      (node (ref "R22") (pin "2") (pinfunction "2_2") (pintype "passive"))
      (node (ref "R23") (pin "1") (pinfunction "1_1") (pintype "passive"))
    )
    (net (code "51") (name "Net-(IC3--IN)") (class "Default")
      (node (ref "C16") (pin "+") (pinfunction "+_+") (pintype "passive"))
      (node (ref "IC3") (pin "2") (pinfunction "-IN_2") (pintype "input"))
      (node (ref "R26") (pin "1") (pinfunction "1_1") (pintype "passive"))
    )
    (net (code "52") (name "Net-(IC3-OUT)") (class "Default")
      (node (ref "IC3") (pin "4") (pinfunction "OUT_4") (pintype "output"))
      (node (ref "K1") (pin "S2") (pinfunction "S_S2") (pintype "passive"))
      (node (ref "R26") (pin "2") (pinfunction "2_2") (pintype "passive"))
      (node (ref "R39") (pin "1") (pinfunction "1_1") (pintype "passive"))
    )
    (net (code "53") (name "Net-(IC4-+IN)") (class "Default")
      (node (ref "IC4") (pin "1") (pinfunction "+IN_1") (pintype "input"))
      (node (ref "R33") (pin "2") (pinfunction "2_2") (pintype "passive"))
      (node (ref "R34") (pin "1") (pinfunction "1_1") (pintype "passive"))
    )
    (net (code "54") (name "Net-(IC4--IN)") (class "Default")
      (node (ref "C19") (pin "+") (pinfunction "+_+") (pintype "passive"))
      (node (ref "IC4") (pin "2") (pinfunction "-IN_2") (pintype "input"))
      (node (ref "R36") (pin "1") (pinfunction "1_1") (pintype "passive"))
    )
    (net (code "55") (name "Net-(IC4-OUT)") (class "Default")
      (node (ref "IC4") (pin "4") (pinfunction "OUT_4") (pintype "output"))
      (node (ref "K1") (pin "S1") (pinfunction "S_S1") (pintype "passive"))
      (node (ref "R36") (pin "2") (pinfunction "2_2") (pintype "passive"))
      (node (ref "R38") (pin "1") (pinfunction "1_1") (pintype "passive"))
    )
    (net (code "56") (name "Net-(IC5A--IN)") (class "Default")
      (node (ref "IC5") (pin "2") (pinfunction "-IN_2") (pintype "input"))
      (node (ref "R43") (pin "2") (pinfunction "2_2") (pintype "passive"))
      (node (ref "R44") (pin "2") (pinfunction "2_2") (pintype "passive"))
    )
    (net (code "57") (name "Net-(IC5A-OUT)") (class "Default")
      (node (ref "IC5") (pin "1") (pinfunction "OUT_1") (pintype "output"))
      (node (ref "R44") (pin "1") (pinfunction "1_1") (pintype "passive"))
      (node (ref "R45") (pin "2") (pinfunction "2_2") (pintype "passive"))
    )
    (net (code "58") (name "Net-(IC6A--IN)") (class "Default")
      (node (ref "IC6") (pin "2") (pinfunction "-IN_2") (pintype "input"))
      (node (ref "R20") (pin "2") (pinfunction "2_2") (pintype "passive"))
      (node (ref "R32") (pin "2") (pinfunction "2_2") (pintype "passive"))
    )
    (net (code "59") (name "Net-(IC6A-OUT)") (class "Default")
      (node (ref "IC6") (pin "1") (pinfunction "OUT_1") (pintype "output"))
      (node (ref "R32") (pin "1") (pinfunction "1_1") (pintype "passive"))
      (node (ref "R37") (pin "2") (pinfunction "2_2") (pintype "passive"))
    )
    (net (code "60") (name "Net-(K1B-P)") (class "Default")
      (node (ref "J3") (pin "1") (pinfunction "1_1") (pintype "passive"))
      (node (ref "K1") (pin "P1") (pinfunction "P_P1") (pintype "passive"))
    )
    (net (code "61") (name "Net-(K1C-P)") (class "Default")
      (node (ref "J3") (pin "3") (pinfunction "3_3") (pintype "passive"))
      (node (ref "K1") (pin "P2") (pinfunction "P_P2") (pintype "passive"))
    )
    (net (code "62") (name "Net-(K2B-P)") (class "Default")
      (node (ref "J6") (pin "1") (pinfunction "1_1") (pintype "passive"))
      (node (ref "K2") (pin "P1") (pinfunction "P_P1") (pintype "passive"))
    )
    (net (code "63") (name "Net-(K2C-P)") (class "Default")
      (node (ref "J6") (pin "3") (pinfunction "3_3") (pintype "passive"))
      (node (ref "K2") (pin "P2") (pinfunction "P_P2") (pintype "passive"))
    )
    (net (code "64") (name "Net-(R21-A)") (class "Default")
      (node (ref "R21") (pin "1") (pinfunction "A_1") (pintype "passive"))
      (node (ref "R29") (pin "1") (pinfunction "1_1") (pintype "passive"))
    )
    (net (code "65") (name "Net-(R21-S)") (class "Default")
      (node (ref "C10") (pin "1") (pinfunction "1_1") (pintype "bidirectional"))
      (node (ref "R21") (pin "2") (pinfunction "S_2") (pintype "passive"))
      (node (ref "U2") (pin "7") (pinfunction "7_7") (pintype "bidirectional"))
    )
    (net (code "66") (name "Net-(R27-Pad2)") (class "Default")
      (node (ref "R27") (pin "2") (pinfunction "2_2") (pintype "passive"))
      (node (ref "R29") (pin "2") (pinfunction "2_2") (pintype "passive"))
      (node (ref "U2") (pin "8") (pinfunction "8_8") (pintype "bidirectional"))
    )
    (net (code "67") (name "Net-(W01A-E)") (class "Default")
      (node (ref "R1") (pin "2") (pinfunction "2_2") (pintype "passive"))
      (node (ref "W01") (pin "1-3") (pinfunction "E_1-3") (pintype "passive"))
    )
    (net (code "68") (name "Net-(W01B-E)") (class "Default")
      (node (ref "R11") (pin "2") (pinfunction "2_2") (pintype "passive"))
      (node (ref "W01") (pin "2-3") (pinfunction "E_2-3") (pintype "passive"))
    )
    (net (code "69") (name "Net-(W03A-S)") (class "Default")
      (node (ref "R4") (pin "2") (pinfunction "2_2") (pintype "passive"))
      (node (ref "R5") (pin "2") (pinfunction "2_2") (pintype "passive"))
      (node (ref "W03") (pin "1-2") (pinfunction "S_1-2") (pintype "passive"))
    )
    (net (code "70") (name "Net-(W03B-S)") (class "Default")
      (node (ref "R14") (pin "2") (pinfunction "2_2") (pintype "passive"))
      (node (ref "R15") (pin "2") (pinfunction "2_2") (pintype "passive"))
      (node (ref "W03") (pin "2-2") (pinfunction "S_2-2") (pintype "passive"))
    )
    (net (code "71") (name "Net-(W04A-S)") (class "Default")
      (node (ref "R33") (pin "1") (pinfunction "1_1") (pintype "passive"))
      (node (ref "W04") (pin "1-2") (pinfunction "S_1-2") (pintype "passive"))
    )
    (net (code "72") (name "Net-(W04B-S)") (class "Default")
      (node (ref "R22") (pin "1") (pinfunction "1_1") (pintype "passive"))
      (node (ref "W04") (pin "2-2") (pinfunction "S_2-2") (pintype "passive"))
    )
    (net (code "73") (name "SUPPLY0_GND_") (class "Default")
      (node (ref "C17") (pin "P$1") (pinfunction "2_P$1") (pintype "bidirectional"))
      (node (ref "C22") (pin "P$2") (pinfunction "1_P$2") (pintype "bidirectional"))
      (node (ref "C23") (pin "P$2") (pinfunction "1_P$2") (pintype "bidirectional"))
      (node (ref "C27") (pin "P$1") (pinfunction "2_P$1") (pintype "bidirectional"))
      (node (ref "C30") (pin "P$2") (pinfunction "1_P$2") (pintype "bidirectional"))
      (node (ref "C4") (pin "P$2") (pinfunction "1_P$2") (pintype "bidirectional"))
      (node (ref "J1") (pin "2") (pinfunction "2_2") (pintype "passive"))
      (node (ref "J2") (pin "2") (pinfunction "2_2") (pintype "passive"))
      (node (ref "J3") (pin "2") (pinfunction "2_2") (pintype "passive"))
      (node (ref "J4") (pin "2") (pinfunction "2_2") (pintype "passive"))
      (node (ref "J6") (pin "2") (pinfunction "2_2") (pintype "passive"))
      (node (ref "R10") (pin "1") (pinfunction "1_1") (pintype "passive"))
      (node (ref "R13") (pin "1") (pinfunction "1_1") (pintype "passive"))
      (node (ref "R17") (pin "2") (pinfunction "2_2") (pintype "passive"))
      (node (ref "R18") (pin "1") (pinfunction "1_1") (pintype "passive"))
      (node (ref "R20") (pin "1") (pinfunction "1_1") (pintype "passive"))
      (node (ref "R23") (pin "2") (pinfunction "2_2") (pintype "passive"))
      (node (ref "R24") (pin "1") (pinfunction "1_1") (pintype "passive"))
      (node (ref "R3") (pin "1") (pinfunction "1_1") (pintype "passive"))
      (node (ref "R34") (pin "2") (pinfunction "2_2") (pintype "passive"))
      (node (ref "R35") (pin "1") (pinfunction "1_1") (pintype "passive"))
      (node (ref "R42") (pin "1") (pinfunction "1_1") (pintype "passive"))
      (node (ref "R43") (pin "1") (pinfunction "1_1") (pintype "passive"))
      (node (ref "R7") (pin "2") (pinfunction "2_2") (pintype "passive"))
      (node (ref "R9") (pin "1") (pinfunction "1_1") (pintype "passive"))
      (node (ref "W01") (pin "1-1") (pinfunction "A_1-1") (pintype "passive"))
      (node (ref "W01") (pin "2-1") (pinfunction "A_2-1") (pintype "passive"))
      (node (ref "W04") (pin "1-1") (pinfunction "A_1-1") (pintype "passive"))
      (node (ref "W04") (pin "2-1") (pinfunction "A_2-1") (pintype "passive"))
    )
    (net (code "74") (name "unconnected-(R21-E-Pad3)") (class "Default")
      (node (ref "R21") (pin "3") (pinfunction "E_3") (pintype "passive"))
    )
  )
)
